# integratedBertha_no_weight.net
KiCad netlist of a schematic drawn in EAGLE
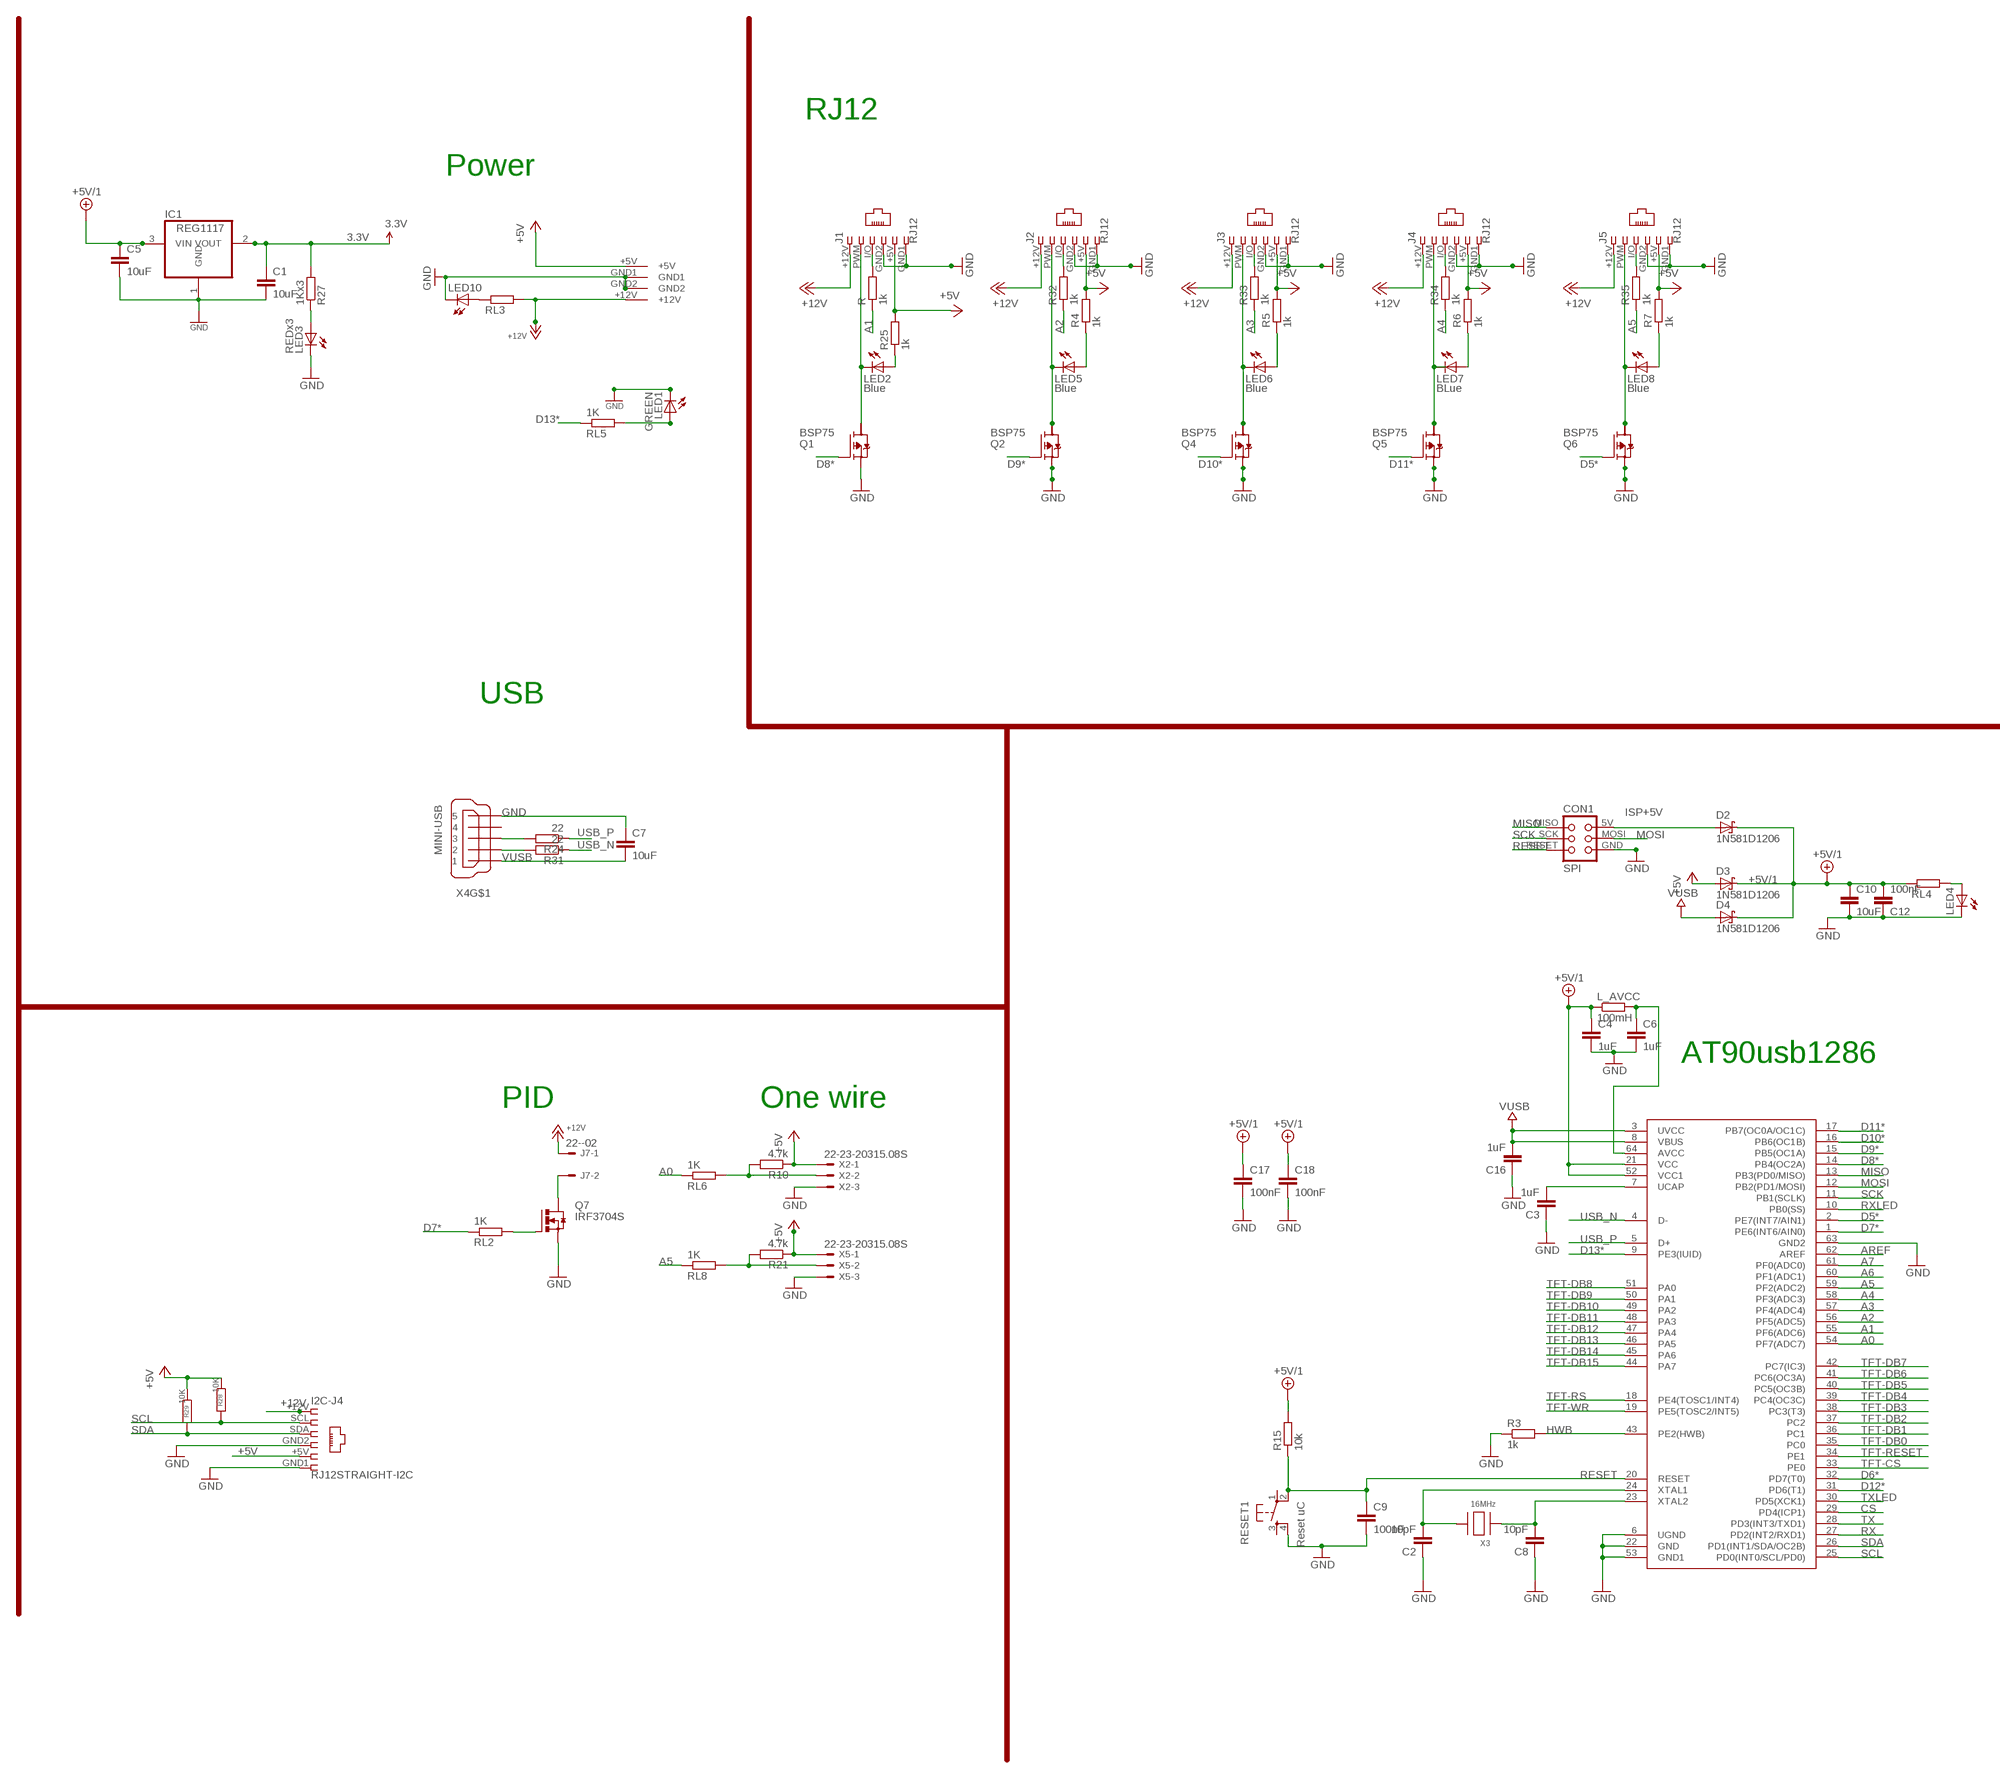
[diagram p0: schematic, sheet 1, part 1 of 2]
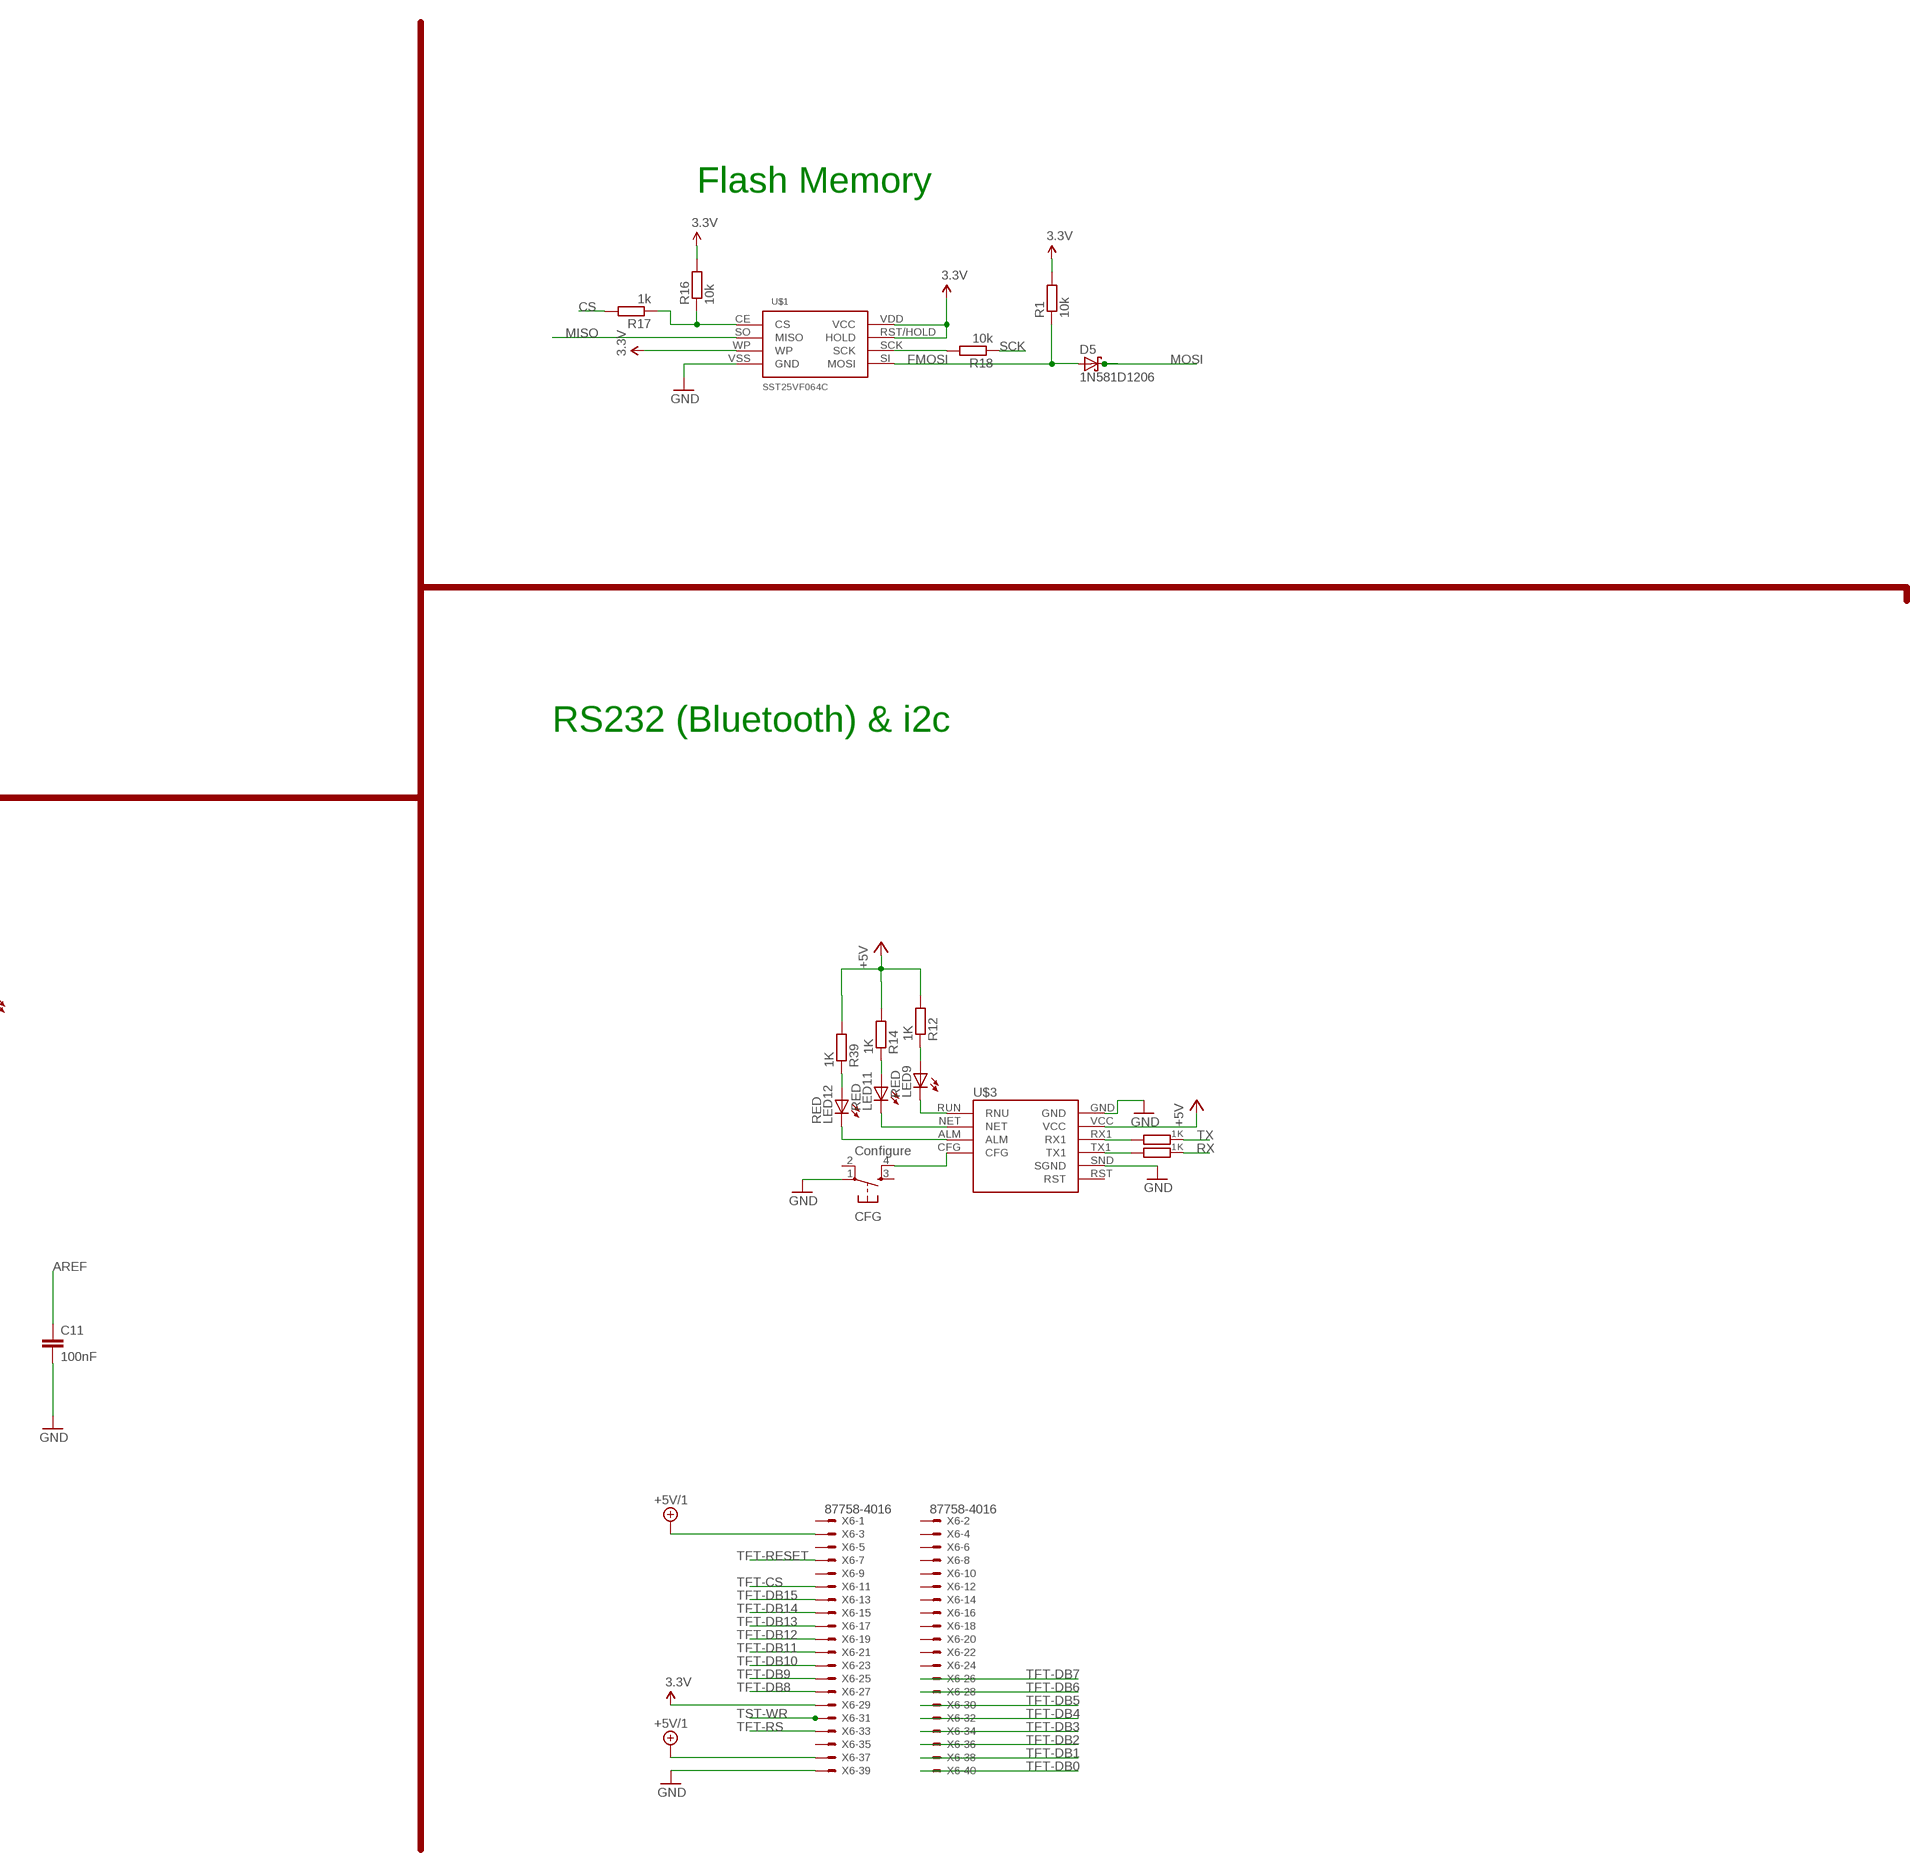
[diagram p1: schematic, sheet 1, part 2 of 2]

(export (version "E")
  (design (tool "Eeschema 10.0.6"))
  (components
    (comp (ref "C1")
      (value "10uF")
      (footprint "eagle-import:C1206")
      (libsource (lib "eagle-import") (part "C-EUC1206"))
    )
    (comp (ref "C2")
      (value "10pF")
      (footprint "eagle-import:C1206")
      (libsource (lib "eagle-import") (part "C-EUC1206"))
    )
    (comp (ref "C3")
      (value "1uF")
      (footprint "eagle-import:C1206")
      (libsource (lib "eagle-import") (part "C-EUC1206"))
    )
    (comp (ref "C4")
      (value "1uF")
      (footprint "eagle-import:C1206")
      (libsource (lib "eagle-import") (part "C-EUC1206"))
    )
    (comp (ref "C5")
      (value "10uF")
      (footprint "eagle-import:C1206")
      (libsource (lib "eagle-import") (part "C-EUC1206"))
    )
    (comp (ref "C6")
      (value "1uF")
      (footprint "eagle-import:C1206")
      (libsource (lib "eagle-import") (part "C-EUC1206"))
    )
    (comp (ref "C7")
      (value "10uF")
      (footprint "eagle-import:C1206")
      (libsource (lib "eagle-import") (part "C-EUC1206"))
    )
    (comp (ref "C8")
      (value "10pF")
      (footprint "eagle-import:C1206")
      (libsource (lib "eagle-import") (part "C-EUC1206"))
    )
    (comp (ref "C9")
      (value "100nF")
      (footprint "eagle-import:C1206")
      (libsource (lib "eagle-import") (part "C-EUC1206"))
    )
    (comp (ref "C10")
      (value "10uF")
      (footprint "eagle-import:C1206")
      (libsource (lib "eagle-import") (part "C-EUC1206"))
    )
    (comp (ref "C11")
      (value "100nF")
      (footprint "eagle-import:C1206")
      (libsource (lib "eagle-import") (part "C-EUC1206"))
    )
    (comp (ref "C12")
      (value "100nF")
      (footprint "eagle-import:C1206")
      (libsource (lib "eagle-import") (part "C-EUC1206"))
    )
    (comp (ref "C16")
      (value "1uF")
      (footprint "eagle-import:C1206")
      (libsource (lib "eagle-import") (part "C-EUC1206"))
    )
    (comp (ref "C17")
      (value "100nF")
      (footprint "eagle-import:C1206")
      (libsource (lib "eagle-import") (part "C-EUC1206"))
    )
    (comp (ref "C18")
      (value "100nF")
      (footprint "eagle-import:C1206")
      (libsource (lib "eagle-import") (part "C-EUC1206"))
    )
    (comp (ref "CFG")
      (value "Configure")
      (footprint "eagle-import:TACTILE_SWITCH_SMD")
      (libsource (lib "eagle-import") (part "TAC_SWITCHSMD"))
    )
    (comp (ref "CON1")
      (value "SPI")
      (footprint "eagle-import:TC2030-MCP-NL")
      (libsource (lib "eagle-import") (part "TINYISPT"))
    )
    (comp (ref "D2")
      (value "1N581D1206")
      (footprint "eagle-import:LED-1206")
      (libsource (lib "eagle-import") (part "1N581D1206"))
    )
    (comp (ref "D3")
      (value "1N581D1206")
      (footprint "eagle-import:LED-1206")
      (libsource (lib "eagle-import") (part "1N581D1206"))
    )
    (comp (ref "D4")
      (value "1N581D1206")
      (footprint "eagle-import:LED-1206")
      (libsource (lib "eagle-import") (part "1N581D1206"))
    )
    (comp (ref "D5")
      (value "1N581D1206")
      (footprint "eagle-import:LED-1206")
      (libsource (lib "eagle-import") (part "1N581D1206"))
    )
    (comp (ref "I2C-J4")
      (value "RJ12STRAIGHT-I2C")
      (footprint "eagle-import:RJ12-STRAIGHT-I2C")
      (libsource (lib "eagle-import") (part "RJ12STRAIGHT-I2C"))
    )
    (comp (ref "IC1")
      (value "REG1117")
      (footprint "eagle-import:SOT223")
      (libsource (lib "eagle-import") (part "REG1117"))
    )
    (comp (ref "J1")
      (value "RJ12")
      (footprint "eagle-import:RJ12-STRAIGHT")
      (libsource (lib "eagle-import") (part "RJ12STRAIGHT"))
    )
    (comp (ref "J2")
      (value "RJ12")
      (footprint "eagle-import:RJ12-STRAIGHT")
      (libsource (lib "eagle-import") (part "RJ12STRAIGHT"))
    )
    (comp (ref "J3")
      (value "RJ12")
      (footprint "eagle-import:RJ12-STRAIGHT")
      (libsource (lib "eagle-import") (part "RJ12STRAIGHT"))
    )
    (comp (ref "J4")
      (value "RJ12")
      (footprint "eagle-import:RJ12-STRAIGHT")
      (libsource (lib "eagle-import") (part "RJ12STRAIGHT"))
    )
    (comp (ref "J5")
      (value "RJ12")
      (footprint "eagle-import:RJ12-STRAIGHT")
      (libsource (lib "eagle-import") (part "RJ12STRAIGHT"))
    )
    (comp (ref "J7")
      (value "22--02")
      (footprint "eagle-import:2-PIN-5.08S")
      (libsource (lib "eagle-import") (part "22-?-02"))
    )
    (comp (ref "LED1")
      (value "GREEN")
      (footprint "eagle-import:CHIPLED_1206")
      (libsource (lib "eagle-import") (part "LEDCHIPLED_1206"))
    )
    (comp (ref "LED2")
      (value "Blue")
      (footprint "eagle-import:CHIPLED_1206")
      (libsource (lib "eagle-import") (part "LEDCHIPLED_1206"))
    )
    (comp (ref "LED3")
      (value "REDx3")
      (footprint "eagle-import:CHIPLED_1206")
      (libsource (lib "eagle-import") (part "LEDCHIPLED_1206"))
    )
    (comp (ref "LED4")
      (value "LEDCHIPLED_1206")
      (footprint "eagle-import:CHIPLED_1206")
      (libsource (lib "eagle-import") (part "LEDCHIPLED_1206"))
    )
    (comp (ref "LED5")
      (value "Blue")
      (footprint "eagle-import:CHIPLED_1206")
      (libsource (lib "eagle-import") (part "LEDCHIPLED_1206"))
    )
    (comp (ref "LED6")
      (value "Blue")
      (footprint "eagle-import:CHIPLED_1206")
      (libsource (lib "eagle-import") (part "LEDCHIPLED_1206"))
    )
    (comp (ref "LED7")
      (value "BLue")
      (footprint "eagle-import:CHIPLED_1206")
      (libsource (lib "eagle-import") (part "LEDCHIPLED_1206"))
    )
    (comp (ref "LED8")
      (value "Blue")
      (footprint "eagle-import:CHIPLED_1206")
      (libsource (lib "eagle-import") (part "LEDCHIPLED_1206"))
    )
    (comp (ref "LED9")
      (value "RED")
      (footprint "eagle-import:CHIPLED_1206")
      (libsource (lib "eagle-import") (part "LEDCHIPLED_1206"))
    )
    (comp (ref "LED10")
      (value "LEDCHIPLED_1206")
      (footprint "eagle-import:CHIPLED_1206")
      (libsource (lib "eagle-import") (part "LEDCHIPLED_1206"))
    )
    (comp (ref "LED11")
      (value "RED")
      (footprint "eagle-import:CHIPLED_1206")
      (libsource (lib "eagle-import") (part "LEDCHIPLED_1206"))
    )
    (comp (ref "LED12")
      (value "RED")
      (footprint "eagle-import:CHIPLED_1206")
      (libsource (lib "eagle-import") (part "LEDCHIPLED_1206"))
    )
    (comp (ref "L_AVCC")
      (value "100mH")
      (footprint "eagle-import:R1206")
      (libsource (lib "eagle-import") (part "resistor_R-EU_R1206"))
    )
    (comp (ref "Q1")
      (value "BSP75")
      (footprint "eagle-import:PG-SOT-223")
      (libsource (lib "eagle-import") (part "BSP613P"))
    )
    (comp (ref "Q2")
      (value "BSP75")
      (footprint "eagle-import:PG-SOT-223")
      (libsource (lib "eagle-import") (part "BSP613P"))
    )
    (comp (ref "Q4")
      (value "BSP75")
      (footprint "eagle-import:PG-SOT-223")
      (libsource (lib "eagle-import") (part "BSP613P"))
    )
    (comp (ref "Q5")
      (value "BSP75")
      (footprint "eagle-import:PG-SOT-223")
      (libsource (lib "eagle-import") (part "BSP613P"))
    )
    (comp (ref "Q6")
      (value "BSP75")
      (footprint "eagle-import:PG-SOT-223")
      (libsource (lib "eagle-import") (part "BSP613P"))
    )
    (comp (ref "Q7")
      (value "IRF3704S")
      (footprint "eagle-import:D2PACK")
      (libsource (lib "eagle-import") (part "IRF3704S"))
    )
    (comp (ref "R")
      (value "1k")
      (footprint "eagle-import:R0805")
      (libsource (lib "eagle-import") (part "R-EU_R0805"))
    )
    (comp (ref "R1")
      (value "10k")
      (footprint "eagle-import:R0805")
      (libsource (lib "eagle-import") (part "R-EU_R0805"))
    )
    (comp (ref "R3")
      (value "1k")
      (footprint "eagle-import:M0805")
      (libsource (lib "eagle-import") (part "resistor_R-EU_M0805"))
    )
    (comp (ref "R4")
      (value "1k")
      (footprint "eagle-import:R0805")
      (libsource (lib "eagle-import") (part "R-EU_R0805"))
    )
    (comp (ref "R5")
      (value "1k")
      (footprint "eagle-import:R0805")
      (libsource (lib "eagle-import") (part "R-EU_R0805"))
    )
    (comp (ref "R6")
      (value "1k")
      (footprint "eagle-import:R0805")
      (libsource (lib "eagle-import") (part "R-EU_R0805"))
    )
    (comp (ref "R7")
      (value "1k")
      (footprint "eagle-import:R0805")
      (libsource (lib "eagle-import") (part "R-EU_R0805"))
    )
    (comp (ref "R8")
      (value "1K")
      (footprint "eagle-import:R0805")
      (libsource (lib "eagle-import") (part "R-EU_R0805"))
    )
    (comp (ref "R10")
      (value "4.7k")
      (footprint "eagle-import:R1206")
      (libsource (lib "eagle-import") (part "resistor_R-EU_R1206"))
    )
    (comp (ref "R11")
      (value "1K")
      (footprint "eagle-import:R0805")
      (libsource (lib "eagle-import") (part "R-EU_R0805"))
    )
    (comp (ref "R12")
      (value "1K")
      (footprint "eagle-import:R0805")
      (libsource (lib "eagle-import") (part "R-EU_R0805"))
    )
    (comp (ref "R14")
      (value "1K")
      (footprint "eagle-import:R0805")
      (libsource (lib "eagle-import") (part "R-EU_R0805"))
    )
    (comp (ref "R15")
      (value "10k")
      (footprint "eagle-import:M0805")
      (libsource (lib "eagle-import") (part "resistor_R-EU_M0805"))
    )
    (comp (ref "R16")
      (value "10k")
      (footprint "eagle-import:R0805")
      (libsource (lib "eagle-import") (part "R-EU_R0805"))
    )
    (comp (ref "R17")
      (value "1k")
      (footprint "eagle-import:R0805")
      (libsource (lib "eagle-import") (part "R-EU_R0805"))
    )
    (comp (ref "R18")
      (value "10k")
      (footprint "eagle-import:R0805")
      (libsource (lib "eagle-import") (part "R-EU_R0805"))
    )
    (comp (ref "R21")
      (value "4.7k")
      (footprint "eagle-import:R1206")
      (libsource (lib "eagle-import") (part "resistor_R-EU_R1206"))
    )
    (comp (ref "R24")
      (value "22")
      (footprint "eagle-import:M1206")
      (libsource (lib "eagle-import") (part "resistor_R-EU_M1206"))
    )
    (comp (ref "R25")
      (value "1k")
      (footprint "eagle-import:R0805")
      (libsource (lib "eagle-import") (part "R-EU_R0805"))
    )
    (comp (ref "R27")
      (value "1Kx3")
      (footprint "eagle-import:R0805")
      (libsource (lib "eagle-import") (part "R-EU_R0805"))
    )
    (comp (ref "R28")
      (value "10K")
      (footprint "eagle-import:M0805")
      (libsource (lib "eagle-import") (part "resistor_R-EU_M0805"))
    )
    (comp (ref "R29")
      (value "10K")
      (footprint "eagle-import:M0805")
      (libsource (lib "eagle-import") (part "resistor_R-EU_M0805"))
    )
    (comp (ref "R31")
      (value "22")
      (footprint "eagle-import:M1206")
      (libsource (lib "eagle-import") (part "resistor_R-EU_M1206"))
    )
    (comp (ref "R32")
      (value "1k")
      (footprint "eagle-import:R0805")
      (libsource (lib "eagle-import") (part "R-EU_R0805"))
    )
    (comp (ref "R33")
      (value "1k")
      (footprint "eagle-import:R0805")
      (libsource (lib "eagle-import") (part "R-EU_R0805"))
    )
    (comp (ref "R34")
      (value "1k")
      (footprint "eagle-import:R0805")
      (libsource (lib "eagle-import") (part "R-EU_R0805"))
    )
    (comp (ref "R35")
      (value "1k")
      (footprint "eagle-import:R0805")
      (libsource (lib "eagle-import") (part "R-EU_R0805"))
    )
    (comp (ref "R39")
      (value "1K")
      (footprint "eagle-import:R0805")
      (libsource (lib "eagle-import") (part "R-EU_R0805"))
    )
    (comp (ref "RESET1")
      (value "Reset uC")
      (footprint "eagle-import:TACTILE_SWITCH_SMD")
      (libsource (lib "eagle-import") (part "TAC_SWITCHSMD"))
    )
    (comp (ref "RL2")
      (value "1K")
      (footprint "eagle-import:R0805")
      (libsource (lib "eagle-import") (part "R-EU_R0805"))
    )
    (comp (ref "RL3")
      (value "R-EU_R0805")
      (footprint "eagle-import:R0805")
      (libsource (lib "eagle-import") (part "R-EU_R0805"))
    )
    (comp (ref "RL4")
      (value "R-EU_R0805")
      (footprint "eagle-import:R0805")
      (libsource (lib "eagle-import") (part "resistor_R-EU_R0805"))
    )
    (comp (ref "RL5")
      (value "1K")
      (footprint "eagle-import:R0805")
      (libsource (lib "eagle-import") (part "R-EU_R0805"))
    )
    (comp (ref "RL6")
      (value "1K")
      (footprint "eagle-import:R0805")
      (libsource (lib "eagle-import") (part "R-EU_R0805"))
    )
    (comp (ref "RL8")
      (value "1K")
      (footprint "eagle-import:R0805")
      (libsource (lib "eagle-import") (part "R-EU_R0805"))
    )
    (comp (ref "U$1")
      (value "SST25VF064C")
      (footprint "eagle-import:SOIC_8-LEAD")
      (libsource (lib "eagle-import") (part "SST25VF064C"))
    )
    (comp (ref "U$2")
      (value "AT90USB1286")
      (footprint "eagle-import:TQFP64")
      (libsource (lib "eagle-import") (part "AT90USB1286TQFP64"))
    )
    (comp (ref "U$3")
      (value "SZ05-ZIGBEETHROUGHHOLE")
      (footprint "eagle-import:SZ05-ZIGBEE4")
      (libsource (lib "eagle-import") (part "SZ05-ZIGBEETHROUGHHOLE"))
    )
    (comp (ref "U$6")
      (value "KPJX-4S-S")
      (footprint "eagle-import:KPJX-4S-S")
      (libsource (lib "eagle-import") (part "KPJX-4S-S"))
    )
    (comp (ref "X2")
      (value "22-23-20315.08S")
      (footprint "eagle-import:3-PIN-5.08S")
      (libsource (lib "eagle-import") (part "22-23-20315.08S"))
    )
    (comp (ref "X3")
      (value "16MHz")
      (footprint "eagle-import:NX6035")
      (libsource (lib "eagle-import") (part "XTALNX6035"))
    )
    (comp (ref "X4")
      (value "MINI-USB")
      (footprint "eagle-import:32005-201")
      (libsource (lib "eagle-import") (part "MINI-USB-SCHIELD-32005-201"))
    )
    (comp (ref "X5")
      (value "22-23-20315.08S")
      (footprint "eagle-import:3-PIN-5.08S")
      (libsource (lib "eagle-import") (part "22-23-20315.08S"))
    )
    (comp (ref "X6")
      (value "87758-4016")
      (footprint "eagle-import:87758-4016")
      (libsource (lib "eagle-import") (part "87758-4016"))
    )
  )
  (nets
    (net (code "1") (name "+5V") (class "Default")
      (node (ref "D3") (pin "A") (pinfunction "A_A") (pintype "passive"))
      (node (ref "I2C-J4") (pin "+5V") (pinfunction "5_+5V") (pintype "bidirectional"))
      (node (ref "J1") (pin "+5V") (pinfunction "5_+5V") (pintype "bidirectional"))
      (node (ref "J2") (pin "+5V") (pinfunction "5_+5V") (pintype "bidirectional"))
      (node (ref "J3") (pin "+5V") (pinfunction "5_+5V") (pintype "bidirectional"))
      (node (ref "J4") (pin "+5V") (pinfunction "5_+5V") (pintype "bidirectional"))
      (node (ref "J5") (pin "+5V") (pinfunction "5_+5V") (pintype "bidirectional"))
      (node (ref "R10") (pin "1") (pinfunction "1_1") (pintype "passive"))
      (node (ref "R12") (pin "2") (pinfunction "2_2") (pintype "passive"))
      (node (ref "R14") (pin "2") (pinfunction "2_2") (pintype "passive"))
      (node (ref "R21") (pin "1") (pinfunction "1_1") (pintype "passive"))
      (node (ref "R25") (pin "2") (pinfunction "2_2") (pintype "passive"))
      (node (ref "R28") (pin "1") (pinfunction "1_1") (pintype "passive"))
      (node (ref "R29") (pin "1") (pinfunction "1_1") (pintype "passive"))
      (node (ref "R39") (pin "2") (pinfunction "2_2") (pintype "passive"))
      (node (ref "R4") (pin "2") (pinfunction "2_2") (pintype "passive"))
      (node (ref "R5") (pin "2") (pinfunction "2_2") (pintype "passive"))
      (node (ref "R6") (pin "2") (pinfunction "2_2") (pintype "passive"))
      (node (ref "R7") (pin "2") (pinfunction "2_2") (pintype "passive"))
      (node (ref "U$3") (pin "VCC") (pinfunction "VCC_VCC") (pintype "bidirectional"))
      (node (ref "U$6") (pin "+5V") (pinfunction "+5V_+5V") (pintype "power_in"))
      (node (ref "X2") (pin "1") (pinfunction "S_1") (pintype "passive"))
      (node (ref "X5") (pin "1") (pinfunction "S_1") (pintype "passive"))
    )
    (net (code "2") (name "+5V{slash}1") (class "Default")
      (node (ref "C10") (pin "1") (pinfunction "1_1") (pintype "passive"))
      (node (ref "C12") (pin "2") (pinfunction "2_2") (pintype "passive"))
      (node (ref "C17") (pin "1") (pinfunction "1_1") (pintype "passive"))
      (node (ref "C18") (pin "1") (pinfunction "1_1") (pintype "passive"))
      (node (ref "C4") (pin "1") (pinfunction "1_1") (pintype "passive"))
      (node (ref "C5") (pin "1") (pinfunction "1_1") (pintype "passive"))
      (node (ref "D2") (pin "C") (pinfunction "C_C") (pintype "passive"))
      (node (ref "D3") (pin "C") (pinfunction "C_C") (pintype "passive"))
      (node (ref "D4") (pin "C") (pinfunction "C_C") (pintype "passive"))
      (node (ref "IC1") (pin "3") (pinfunction "VIN_3") (pintype "input"))
      (node (ref "L_AVCC") (pin "1") (pinfunction "1_1") (pintype "passive"))
      (node (ref "R15") (pin "2") (pinfunction "2_2") (pintype "passive"))
      (node (ref "RL4") (pin "1") (pinfunction "1_1") (pintype "passive"))
      (node (ref "U$2") (pin "21") (pinfunction "VCC_21") (pintype "bidirectional"))
      (node (ref "U$2") (pin "52") (pinfunction "VCC1_52") (pintype "bidirectional"))
      (node (ref "X6") (pin "3") (pinfunction "S_3") (pintype "passive"))
      (node (ref "X6") (pin "37") (pinfunction "S_37") (pintype "passive"))
    )
    (net (code "3") (name "+12V") (class "Default")
      (node (ref "I2C-J4") (pin "+12V") (pinfunction "1_+12V") (pintype "bidirectional"))
      (node (ref "J1") (pin "+12V") (pinfunction "1_+12V") (pintype "bidirectional"))
      (node (ref "J2") (pin "+12V") (pinfunction "1_+12V") (pintype "bidirectional"))
      (node (ref "J3") (pin "+12V") (pinfunction "1_+12V") (pintype "bidirectional"))
      (node (ref "J4") (pin "+12V") (pinfunction "1_+12V") (pintype "bidirectional"))
      (node (ref "J5") (pin "+12V") (pinfunction "1_+12V") (pintype "bidirectional"))
      (node (ref "J7") (pin "1") (pinfunction "S_1") (pintype "passive"))
      (node (ref "RL3") (pin "2") (pinfunction "2_2") (pintype "passive"))
      (node (ref "U$6") (pin "+12V") (pinfunction "+12V_+12V") (pintype "power_in"))
    )
    (net (code "4") (name "/A0") (class "Default")
      (node (ref "RL6") (pin "1") (pinfunction "1_1") (pintype "passive"))
      (node (ref "U$2") (pin "54") (pinfunction "PF7(ADC7)_54") (pintype "bidirectional"))
    )
    (net (code "5") (name "/A1") (class "Default")
      (node (ref "R") (pin "1") (pinfunction "1_1") (pintype "passive"))
      (node (ref "U$2") (pin "55") (pinfunction "PF6(ADC6)_55") (pintype "bidirectional"))
    )
    (net (code "6") (name "/A2") (class "Default")
      (node (ref "R32") (pin "1") (pinfunction "1_1") (pintype "passive"))
      (node (ref "U$2") (pin "56") (pinfunction "PF5(ADC5)_56") (pintype "bidirectional"))
    )
    (net (code "7") (name "/A3") (class "Default")
      (node (ref "R33") (pin "1") (pinfunction "1_1") (pintype "passive"))
      (node (ref "U$2") (pin "57") (pinfunction "PF4(ADC4)_57") (pintype "bidirectional"))
    )
    (net (code "8") (name "/A4") (class "Default")
      (node (ref "R34") (pin "1") (pinfunction "1_1") (pintype "passive"))
      (node (ref "U$2") (pin "58") (pinfunction "PF3(ADC3)_58") (pintype "bidirectional"))
    )
    (net (code "9") (name "/A5") (class "Default")
      (node (ref "R35") (pin "1") (pinfunction "1_1") (pintype "passive"))
      (node (ref "RL8") (pin "1") (pinfunction "1_1") (pintype "passive"))
      (node (ref "U$2") (pin "59") (pinfunction "PF2(ADC2)_59") (pintype "bidirectional"))
    )
    (net (code "10") (name "/A6") (class "Default")
      (node (ref "U$2") (pin "60") (pinfunction "PF1(ADC1)_60") (pintype "bidirectional"))
    )
    (net (code "11") (name "/A7") (class "Default")
      (node (ref "U$2") (pin "61") (pinfunction "PF0(ADC0)_61") (pintype "bidirectional"))
    )
    (net (code "12") (name "/AREF") (class "Default")
      (node (ref "C11") (pin "1") (pinfunction "1_1") (pintype "passive"))
      (node (ref "U$2") (pin "62") (pinfunction "AREF_62") (pintype "bidirectional"))
    )
    (net (code "13") (name "/CS") (class "Default")
      (node (ref "R17") (pin "2") (pinfunction "2_2") (pintype "passive"))
      (node (ref "U$2") (pin "29") (pinfunction "PD4(ICP1)_29") (pintype "bidirectional"))
    )
    (net (code "14") (name "/D5*") (class "Default")
      (node (ref "Q6") (pin "1") (pinfunction "G_1") (pintype "passive"))
      (node (ref "U$2") (pin "2") (pinfunction "PE7(INT7/AIN1)_2") (pintype "bidirectional"))
    )
    (net (code "15") (name "/D6*") (class "Default")
      (node (ref "U$2") (pin "32") (pinfunction "PD7(T0)_32") (pintype "bidirectional"))
    )
    (net (code "16") (name "/D7*") (class "Default")
      (node (ref "RL2") (pin "1") (pinfunction "1_1") (pintype "passive"))
      (node (ref "U$2") (pin "1") (pinfunction "PE6(INT6/AIN0)_1") (pintype "bidirectional"))
    )
    (net (code "17") (name "/D8*") (class "Default")
      (node (ref "Q1") (pin "1") (pinfunction "G_1") (pintype "passive"))
      (node (ref "U$2") (pin "14") (pinfunction "PB4(OC2A)_14") (pintype "bidirectional"))
    )
    (net (code "18") (name "/D9*") (class "Default")
      (node (ref "Q2") (pin "1") (pinfunction "G_1") (pintype "passive"))
      (node (ref "U$2") (pin "15") (pinfunction "PB5(OC1A)_15") (pintype "bidirectional"))
    )
    (net (code "19") (name "/D10*") (class "Default")
      (node (ref "Q4") (pin "1") (pinfunction "G_1") (pintype "passive"))
      (node (ref "U$2") (pin "16") (pinfunction "PB6(OC1B)_16") (pintype "bidirectional"))
    )
    (net (code "20") (name "/D11*") (class "Default")
      (node (ref "Q5") (pin "1") (pinfunction "G_1") (pintype "passive"))
      (node (ref "U$2") (pin "17") (pinfunction "PB7(OC0A/OC1C)_17") (pintype "bidirectional"))
    )
    (net (code "21") (name "/D12*") (class "Default")
      (node (ref "U$2") (pin "31") (pinfunction "PD6(T1)_31") (pintype "bidirectional"))
    )
    (net (code "22") (name "/D13*") (class "Default")
      (node (ref "RL5") (pin "1") (pinfunction "1_1") (pintype "passive"))
      (node (ref "U$2") (pin "9") (pinfunction "PE3(IUID)_9") (pintype "bidirectional"))
    )
    (net (code "23") (name "/FMOSI") (class "Default")
      (node (ref "D5") (pin "A") (pinfunction "A_A") (pintype "passive"))
      (node (ref "R1") (pin "1") (pinfunction "1_1") (pintype "passive"))
      (node (ref "U$1") (pin "SI") (pinfunction "MOSI_SI") (pintype "bidirectional"))
    )
    (net (code "24") (name "/HWB") (class "Default")
      (node (ref "R3") (pin "2") (pinfunction "2_2") (pintype "passive"))
      (node (ref "U$2") (pin "43") (pinfunction "PE2(HWB)_43") (pintype "bidirectional"))
    )
    (net (code "25") (name "/ISP+5V") (class "Default")
      (node (ref "CON1") (pin "5V") (pinfunction "VCC_5V") (pintype "passive"))
      (node (ref "D2") (pin "A") (pinfunction "A_A") (pintype "passive"))
    )
    (net (code "26") (name "/MISO") (class "Default")
      (node (ref "CON1") (pin "MISO") (pinfunction "MISO_MISO") (pintype "passive"))
      (node (ref "U$1") (pin "SO") (pinfunction "MISO_SO") (pintype "bidirectional"))
      (node (ref "U$2") (pin "13") (pinfunction "PB3(PD0/MISO)_13") (pintype "bidirectional"))
    )
    (net (code "27") (name "/MOSI") (class "Default")
      (node (ref "CON1") (pin "MOSI") (pinfunction "MOSI_MOSI") (pintype "passive"))
      (node (ref "D5") (pin "C") (pinfunction "C_C") (pintype "passive"))
      (node (ref "U$2") (pin "12") (pinfunction "PB2(PD1/MOSI)_12") (pintype "bidirectional"))
    )
    (net (code "28") (name "/RESET") (class "Default")
      (node (ref "C9") (pin "1") (pinfunction "1_1") (pintype "passive"))
      (node (ref "CON1") (pin "RESET") (pinfunction "RESET_RESET") (pintype "passive"))
      (node (ref "R15") (pin "1") (pinfunction "1_1") (pintype "passive"))
      (node (ref "RESET1") (pin "2") (pinfunction "2_2") (pintype "passive"))
      (node (ref "U$2") (pin "20") (pinfunction "RESET_20") (pintype "bidirectional"))
    )
    (net (code "29") (name "/RX") (class "Default")
      (node (ref "R8") (pin "1") (pinfunction "1_1") (pintype "passive"))
      (node (ref "U$2") (pin "27") (pinfunction "PD2(INT2/RXD1)_27") (pintype "bidirectional"))
    )
    (net (code "30") (name "/RXLED") (class "Default")
      (node (ref "U$2") (pin "10") (pinfunction "PB0(SS)_10") (pintype "bidirectional"))
    )
    (net (code "31") (name "/SCK") (class "Default")
      (node (ref "CON1") (pin "SCK") (pinfunction "SCK_SCK") (pintype "passive"))
      (node (ref "R18") (pin "1") (pinfunction "1_1") (pintype "passive"))
      (node (ref "U$2") (pin "11") (pinfunction "PB1(SCLK)_11") (pintype "bidirectional"))
    )
    (net (code "32") (name "/SCL") (class "Default")
      (node (ref "I2C-J4") (pin "SCL") (pinfunction "2_SCL") (pintype "bidirectional"))
      (node (ref "R28") (pin "2") (pinfunction "2_2") (pintype "passive"))
      (node (ref "U$2") (pin "25") (pinfunction "PD0(INT0/SCL/PD0)_25") (pintype "bidirectional"))
    )
    (net (code "33") (name "/SDA") (class "Default")
      (node (ref "I2C-J4") (pin "SDA") (pinfunction "3_SDA") (pintype "bidirectional"))
      (node (ref "R29") (pin "2") (pinfunction "2_2") (pintype "passive"))
      (node (ref "U$2") (pin "26") (pinfunction "PD1(INT1/SDA/OC2B)_26") (pintype "bidirectional"))
    )
    (net (code "34") (name "/TFT-CS") (class "Default")
      (node (ref "U$2") (pin "33") (pinfunction "PE0_33") (pintype "bidirectional"))
      (node (ref "X6") (pin "11") (pinfunction "S_11") (pintype "passive"))
    )
    (net (code "35") (name "/TFT-DB0") (class "Default")
      (node (ref "U$2") (pin "35") (pinfunction "PC0_35") (pintype "bidirectional"))
      (node (ref "X6") (pin "40") (pinfunction "S_40") (pintype "passive"))
    )
    (net (code "36") (name "/TFT-DB1") (class "Default")
      (node (ref "U$2") (pin "36") (pinfunction "PC1_36") (pintype "bidirectional"))
      (node (ref "X6") (pin "38") (pinfunction "S_38") (pintype "passive"))
    )
    (net (code "37") (name "/TFT-DB2") (class "Default")
      (node (ref "U$2") (pin "37") (pinfunction "PC2_37") (pintype "bidirectional"))
      (node (ref "X6") (pin "36") (pinfunction "S_36") (pintype "passive"))
    )
    (net (code "38") (name "/TFT-DB3") (class "Default")
      (node (ref "U$2") (pin "38") (pinfunction "PC3(T3)_38") (pintype "bidirectional"))
      (node (ref "X6") (pin "34") (pinfunction "S_34") (pintype "passive"))
    )
    (net (code "39") (name "/TFT-DB4") (class "Default")
      (node (ref "U$2") (pin "39") (pinfunction "PC4(OC3C)_39") (pintype "bidirectional"))
      (node (ref "X6") (pin "32") (pinfunction "S_32") (pintype "passive"))
    )
    (net (code "40") (name "/TFT-DB5") (class "Default")
      (node (ref "U$2") (pin "40") (pinfunction "PC5(OC3B)_40") (pintype "bidirectional"))
      (node (ref "X6") (pin "30") (pinfunction "S_30") (pintype "passive"))
    )
    (net (code "41") (name "/TFT-DB6") (class "Default")
      (node (ref "U$2") (pin "41") (pinfunction "PC6(OC3A)_41") (pintype "bidirectional"))
      (node (ref "X6") (pin "28") (pinfunction "S_28") (pintype "passive"))
    )
    (net (code "42") (name "/TFT-DB7") (class "Default")
      (node (ref "U$2") (pin "42") (pinfunction "PC7(IC3)_42") (pintype "bidirectional"))
      (node (ref "X6") (pin "26") (pinfunction "S_26") (pintype "passive"))
    )
    (net (code "43") (name "/TFT-DB8") (class "Default")
      (node (ref "U$2") (pin "51") (pinfunction "PA0_51") (pintype "bidirectional"))
      (node (ref "X6") (pin "27") (pinfunction "S_27") (pintype "passive"))
    )
    (net (code "44") (name "/TFT-DB9") (class "Default")
      (node (ref "U$2") (pin "50") (pinfunction "PA1_50") (pintype "bidirectional"))
      (node (ref "X6") (pin "25") (pinfunction "S_25") (pintype "passive"))
    )
    (net (code "45") (name "/TFT-DB10") (class "Default")
      (node (ref "U$2") (pin "49") (pinfunction "PA2_49") (pintype "bidirectional"))
      (node (ref "X6") (pin "23") (pinfunction "S_23") (pintype "passive"))
    )
    (net (code "46") (name "/TFT-DB11") (class "Default")
      (node (ref "U$2") (pin "48") (pinfunction "PA3_48") (pintype "bidirectional"))
      (node (ref "X6") (pin "21") (pinfunction "S_21") (pintype "passive"))
    )
    (net (code "47") (name "/TFT-DB12") (class "Default")
      (node (ref "U$2") (pin "47") (pinfunction "PA4_47") (pintype "bidirectional"))
      (node (ref "X6") (pin "19") (pinfunction "S_19") (pintype "passive"))
    )
    (net (code "48") (name "/TFT-DB13") (class "Default")
      (node (ref "U$2") (pin "46") (pinfunction "PA5_46") (pintype "bidirectional"))
      (node (ref "X6") (pin "17") (pinfunction "S_17") (pintype "passive"))
    )
    (net (code "49") (name "/TFT-DB14") (class "Default")
      (node (ref "U$2") (pin "45") (pinfunction "PA6_45") (pintype "bidirectional"))
      (node (ref "X6") (pin "15") (pinfunction "S_15") (pintype "passive"))
    )
    (net (code "50") (name "/TFT-DB15") (class "Default")
      (node (ref "U$2") (pin "44") (pinfunction "PA7_44") (pintype "bidirectional"))
      (node (ref "X6") (pin "13") (pinfunction "S_13") (pintype "passive"))
    )
    (net (code "51") (name "/TFT-RESET") (class "Default")
      (node (ref "U$2") (pin "34") (pinfunction "PE1_34") (pintype "bidirectional"))
      (node (ref "X6") (pin "7") (pinfunction "S_7") (pintype "passive"))
    )
    (net (code "52") (name "/TFT-RS") (class "Default")
      (node (ref "U$2") (pin "18") (pinfunction "PE4(TOSC1/INT4)_18") (pintype "bidirectional"))
      (node (ref "X6") (pin "33") (pinfunction "S_33") (pintype "passive"))
    )
    (net (code "53") (name "/TFT-WR") (class "Default")
      (node (ref "U$2") (pin "19") (pinfunction "PE5(TOSC2/INT5)_19") (pintype "bidirectional"))
    )
    (net (code "54") (name "/TST-WR") (class "Default")
      (node (ref "X6") (pin "31") (pinfunction "S_31") (pintype "passive"))
    )
    (net (code "55") (name "/TX") (class "Default")
      (node (ref "R11") (pin "1") (pinfunction "1_1") (pintype "passive"))
      (node (ref "U$2") (pin "28") (pinfunction "PD3(INT3/TXD1)_28") (pintype "bidirectional"))
    )
    (net (code "56") (name "/TXLED") (class "Default")
      (node (ref "U$2") (pin "30") (pinfunction "PD5(XCK1)_30") (pintype "bidirectional"))
    )
    (net (code "57") (name "/USB_N") (class "Default")
      (node (ref "R31") (pin "1") (pinfunction "1_1") (pintype "passive"))
      (node (ref "U$2") (pin "4") (pinfunction "D-_4") (pintype "bidirectional"))
    )
    (net (code "58") (name "/USB_P") (class "Default")
      (node (ref "R24") (pin "1") (pinfunction "1_1") (pintype "passive"))
      (node (ref "U$2") (pin "5") (pinfunction "D+_5") (pintype "bidirectional"))
    )
    (net (code "59") (name "3.3V") (class "Default")
      (node (ref "C1") (pin "1") (pinfunction "1_1") (pintype "passive"))
      (node (ref "IC1") (pin "2") (pinfunction "VOUT_2") (pintype "output"))
      (node (ref "R1") (pin "2") (pinfunction "2_2") (pintype "passive"))
      (node (ref "R16") (pin "2") (pinfunction "2_2") (pintype "passive"))
      (node (ref "R27") (pin "2") (pinfunction "2_2") (pintype "passive"))
      (node (ref "U$1") (pin "RST/HOLD") (pinfunction "HOLD_RST/HOLD") (pintype "bidirectional"))
      (node (ref "U$1") (pin "VDD") (pinfunction "VCC_VDD") (pintype "bidirectional"))
      (node (ref "U$1") (pin "WP") (pinfunction "WP_WP") (pintype "bidirectional"))
      (node (ref "X6") (pin "29") (pinfunction "S_29") (pintype "passive"))
    )
    (net (code "60") (name "GND") (class "Default")
      (node (ref "C1") (pin "2") (pinfunction "2_2") (pintype "passive"))
      (node (ref "C10") (pin "2") (pinfunction "2_2") (pintype "passive"))
      (node (ref "C11") (pin "2") (pinfunction "2_2") (pintype "passive"))
      (node (ref "C12") (pin "1") (pinfunction "1_1") (pintype "passive"))
      (node (ref "C16") (pin "1") (pinfunction "1_1") (pintype "passive"))
      (node (ref "C17") (pin "2") (pinfunction "2_2") (pintype "passive"))
      (node (ref "C18") (pin "2") (pinfunction "2_2") (pintype "passive"))
      (node (ref "C2") (pin "1") (pinfunction "1_1") (pintype "passive"))
      (node (ref "C3") (pin "1") (pinfunction "1_1") (pintype "passive"))
      (node (ref "C4") (pin "2") (pinfunction "2_2") (pintype "passive"))
      (node (ref "C5") (pin "2") (pinfunction "2_2") (pintype "passive"))
      (node (ref "C6") (pin "2") (pinfunction "2_2") (pintype "passive"))
      (node (ref "C7") (pin "1") (pinfunction "1_1") (pintype "passive"))
      (node (ref "C8") (pin "1") (pinfunction "1_1") (pintype "passive"))
      (node (ref "C9") (pin "2") (pinfunction "2_2") (pintype "passive"))
      (node (ref "CFG") (pin "1") (pinfunction "1_1") (pintype "passive"))
      (node (ref "CON1") (pin "GND") (pinfunction "GND_GND") (pintype "passive"))
      (node (ref "I2C-J4") (pin "GND1") (pinfunction "6_GND1") (pintype "bidirectional"))
      (node (ref "I2C-J4") (pin "GND2") (pinfunction "4_GND2") (pintype "bidirectional"))
      (node (ref "IC1") (pin "1") (pinfunction "GND_1") (pintype "power_in"))
      (node (ref "J1") (pin "GND1") (pinfunction "6_GND1") (pintype "bidirectional"))
      (node (ref "J1") (pin "GND2") (pinfunction "4_GND2") (pintype "bidirectional"))
      (node (ref "J2") (pin "GND1") (pinfunction "6_GND1") (pintype "bidirectional"))
      (node (ref "J2") (pin "GND2") (pinfunction "4_GND2") (pintype "bidirectional"))
      (node (ref "J3") (pin "GND1") (pinfunction "6_GND1") (pintype "bidirectional"))
      (node (ref "J3") (pin "GND2") (pinfunction "4_GND2") (pintype "bidirectional"))
      (node (ref "J4") (pin "GND1") (pinfunction "6_GND1") (pintype "bidirectional"))
      (node (ref "J4") (pin "GND2") (pinfunction "4_GND2") (pintype "bidirectional"))
      (node (ref "J5") (pin "GND1") (pinfunction "6_GND1") (pintype "bidirectional"))
      (node (ref "J5") (pin "GND2") (pinfunction "4_GND2") (pintype "bidirectional"))
      (node (ref "LED1") (pin "C") (pinfunction "C_C") (pintype "passive"))
      (node (ref "LED10") (pin "C") (pinfunction "C_C") (pintype "passive"))
      (node (ref "LED3") (pin "C") (pinfunction "C_C") (pintype "passive"))
      (node (ref "LED4") (pin "C") (pinfunction "C_C") (pintype "passive"))
      (node (ref "Q1") (pin "3") (pinfunction "S_3") (pintype "passive"))
      (node (ref "Q2") (pin "3") (pinfunction "S_3") (pintype "passive"))
      (node (ref "Q4") (pin "3") (pinfunction "S_3") (pintype "passive"))
      (node (ref "Q5") (pin "3") (pinfunction "S_3") (pintype "passive"))
      (node (ref "Q6") (pin "3") (pinfunction "S_3") (pintype "passive"))
      (node (ref "Q7") (pin "3") (pinfunction "S_3") (pintype "passive"))
      (node (ref "R3") (pin "1") (pinfunction "1_1") (pintype "passive"))
      (node (ref "RESET1") (pin "4") (pinfunction "4_4") (pintype "passive"))
      (node (ref "U$1") (pin "VSS") (pinfunction "GND_VSS") (pintype "bidirectional"))
      (node (ref "U$2") (pin "22") (pinfunction "GND_22") (pintype "bidirectional"))
      (node (ref "U$2") (pin "53") (pinfunction "GND1_53") (pintype "bidirectional"))
      (node (ref "U$2") (pin "6") (pinfunction "UGND_6") (pintype "bidirectional"))
      (node (ref "U$2") (pin "63") (pinfunction "GND2_63") (pintype "bidirectional"))
      (node (ref "U$3") (pin "GND") (pinfunction "GND_GND") (pintype "bidirectional"))
      (node (ref "U$3") (pin "SND") (pinfunction "SGND_SND") (pintype "bidirectional"))
      (node (ref "U$6") (pin "GND1") (pinfunction "GND1_GND1") (pintype "input"))
      (node (ref "U$6") (pin "GND2") (pinfunction "GND2_GND2") (pintype "input"))
      (node (ref "X2") (pin "3") (pinfunction "S_3") (pintype "passive"))
      (node (ref "X4") (pin "5") (pinfunction "5_5") (pintype "passive"))
      (node (ref "X5") (pin "3") (pinfunction "S_3") (pintype "passive"))
      (node (ref "X6") (pin "39") (pinfunction "S_39") (pintype "passive"))
    )
    (net (code "61") (name "Net-(CFG-Pad4)") (class "Default")
      (node (ref "CFG") (pin "4") (pinfunction "4_4") (pintype "passive"))
      (node (ref "U$3") (pin "CFG") (pinfunction "CFG_CFG") (pintype "bidirectional"))
    )
    (net (code "62") (name "Net-(J1-2)") (class "Default")
      (node (ref "J1") (pin "PWM") (pinfunction "2_PWM") (pintype "bidirectional"))
      (node (ref "LED2") (pin "C") (pinfunction "C_C") (pintype "passive"))
      (node (ref "Q1") (pin "2") (pinfunction "D_2") (pintype "passive"))
    )
    (net (code "63") (name "Net-(J1-3)") (class "Default")
      (node (ref "J1") (pin "I/O") (pinfunction "3_I/O") (pintype "bidirectional"))
      (node (ref "R") (pin "2") (pinfunction "2_2") (pintype "passive"))
    )
    (net (code "64") (name "Net-(J2-2)") (class "Default")
      (node (ref "J2") (pin "PWM") (pinfunction "2_PWM") (pintype "bidirectional"))
      (node (ref "LED5") (pin "C") (pinfunction "C_C") (pintype "passive"))
      (node (ref "Q2") (pin "2") (pinfunction "D_2") (pintype "passive"))
    )
    (net (code "65") (name "Net-(J2-3)") (class "Default")
      (node (ref "J2") (pin "I/O") (pinfunction "3_I/O") (pintype "bidirectional"))
      (node (ref "R32") (pin "2") (pinfunction "2_2") (pintype "passive"))
    )
    (net (code "66") (name "Net-(J3-2)") (class "Default")
      (node (ref "J3") (pin "PWM") (pinfunction "2_PWM") (pintype "bidirectional"))
      (node (ref "LED6") (pin "C") (pinfunction "C_C") (pintype "passive"))
      (node (ref "Q4") (pin "2") (pinfunction "D_2") (pintype "passive"))
    )
    (net (code "67") (name "Net-(J3-3)") (class "Default")
      (node (ref "J3") (pin "I/O") (pinfunction "3_I/O") (pintype "bidirectional"))
      (node (ref "R33") (pin "2") (pinfunction "2_2") (pintype "passive"))
    )
    (net (code "68") (name "Net-(J4-2)") (class "Default")
      (node (ref "J4") (pin "PWM") (pinfunction "2_PWM") (pintype "bidirectional"))
      (node (ref "LED7") (pin "C") (pinfunction "C_C") (pintype "passive"))
      (node (ref "Q5") (pin "2") (pinfunction "D_2") (pintype "passive"))
    )
    (net (code "69") (name "Net-(J4-3)") (class "Default")
      (node (ref "J4") (pin "I/O") (pinfunction "3_I/O") (pintype "bidirectional"))
      (node (ref "R34") (pin "2") (pinfunction "2_2") (pintype "passive"))
    )
    (net (code "70") (name "Net-(J5-2)") (class "Default")
      (node (ref "J5") (pin "PWM") (pinfunction "2_PWM") (pintype "bidirectional"))
      (node (ref "LED8") (pin "C") (pinfunction "C_C") (pintype "passive"))
      (node (ref "Q6") (pin "2") (pinfunction "D_2") (pintype "passive"))
    )
    (net (code "71") (name "Net-(J5-3)") (class "Default")
      (node (ref "J5") (pin "I/O") (pinfunction "3_I/O") (pintype "bidirectional"))
      (node (ref "R35") (pin "2") (pinfunction "2_2") (pintype "passive"))
    )
    (net (code "72") (name "Net-(J7B-S)") (class "Default")
      (node (ref "J7") (pin "2") (pinfunction "S_2") (pintype "passive"))
      (node (ref "Q7") (pin "2") (pinfunction "D_2") (pintype "passive"))
    )
    (net (code "73") (name "Net-(LED1-PadA)") (class "Default")
      (node (ref "LED1") (pin "A") (pinfunction "A_A") (pintype "passive"))
      (node (ref "RL5") (pin "2") (pinfunction "2_2") (pintype "passive"))
    )
    (net (code "74") (name "Net-(LED2-PadA)") (class "Default")
      (node (ref "LED2") (pin "A") (pinfunction "A_A") (pintype "passive"))
      (node (ref "R25") (pin "1") (pinfunction "1_1") (pintype "passive"))
    )
    (net (code "75") (name "Net-(LED3-PadA)") (class "Default")
      (node (ref "LED3") (pin "A") (pinfunction "A_A") (pintype "passive"))
      (node (ref "R27") (pin "1") (pinfunction "1_1") (pintype "passive"))
    )
    (net (code "76") (name "Net-(LED4-PadA)") (class "Default")
      (node (ref "LED4") (pin "A") (pinfunction "A_A") (pintype "passive"))
      (node (ref "RL4") (pin "2") (pinfunction "2_2") (pintype "passive"))
    )
    (net (code "77") (name "Net-(LED5-PadA)") (class "Default")
      (node (ref "LED5") (pin "A") (pinfunction "A_A") (pintype "passive"))
      (node (ref "R4") (pin "1") (pinfunction "1_1") (pintype "passive"))
    )
    (net (code "78") (name "Net-(LED6-PadA)") (class "Default")
      (node (ref "LED6") (pin "A") (pinfunction "A_A") (pintype "passive"))
      (node (ref "R5") (pin "1") (pinfunction "1_1") (pintype "passive"))
    )
    (net (code "79") (name "Net-(LED7-PadA)") (class "Default")
      (node (ref "LED7") (pin "A") (pinfunction "A_A") (pintype "passive"))
      (node (ref "R6") (pin "1") (pinfunction "1_1") (pintype "passive"))
    )
    (net (code "80") (name "Net-(LED8-PadA)") (class "Default")
      (node (ref "LED8") (pin "A") (pinfunction "A_A") (pintype "passive"))
      (node (ref "R7") (pin "1") (pinfunction "1_1") (pintype "passive"))
    )
    (net (code "81") (name "Net-(LED9-PadA)") (class "Default")
      (node (ref "LED9") (pin "A") (pinfunction "A_A") (pintype "passive"))
      (node (ref "R12") (pin "1") (pinfunction "1_1") (pintype "passive"))
    )
    (net (code "82") (name "Net-(LED10-PadA)") (class "Default")
      (node (ref "LED10") (pin "A") (pinfunction "A_A") (pintype "passive"))
      (node (ref "RL3") (pin "1") (pinfunction "1_1") (pintype "passive"))
    )
    (net (code "83") (name "Net-(LED11-PadA)") (class "Default")
      (node (ref "LED11") (pin "A") (pinfunction "A_A") (pintype "passive"))
      (node (ref "R14") (pin "1") (pinfunction "1_1") (pintype "passive"))
    )
    (net (code "84") (name "Net-(LED11-PadC)") (class "Default")
      (node (ref "LED11") (pin "C") (pinfunction "C_C") (pintype "passive"))
      (node (ref "U$3") (pin "NET") (pinfunction "NET_NET") (pintype "bidirectional"))
    )
    (net (code "85") (name "Net-(LED12-PadA)") (class "Default")
      (node (ref "LED12") (pin "A") (pinfunction "A_A") (pintype "passive"))
      (node (ref "R39") (pin "1") (pinfunction "1_1") (pintype "passive"))
    )
    (net (code "86") (name "Net-(LED12-PadC)") (class "Default")
      (node (ref "LED12") (pin "C") (pinfunction "C_C") (pintype "passive"))
      (node (ref "U$3") (pin "ALM") (pinfunction "ALM_ALM") (pintype "bidirectional"))
    )
    (net (code "87") (name "Net-(Q7-G)") (class "Default")
      (node (ref "Q7") (pin "1") (pinfunction "G_1") (pintype "passive"))
      (node (ref "RL2") (pin "2") (pinfunction "2_2") (pintype "passive"))
    )
    (net (code "88") (name "Net-(R8-Pad2)") (class "Default")
      (node (ref "R8") (pin "2") (pinfunction "2_2") (pintype "passive"))
      (node (ref "U$3") (pin "TX1") (pinfunction "TX1_TX1") (pintype "bidirectional"))
    )
    (net (code "89") (name "Net-(R11-Pad2)") (class "Default")
      (node (ref "R11") (pin "2") (pinfunction "2_2") (pintype "passive"))
      (node (ref "U$3") (pin "RX1") (pinfunction "RX1_RX1") (pintype "bidirectional"))
    )
    (net (code "90") (name "Net-(R18-Pad2)") (class "Default")
      (node (ref "R18") (pin "2") (pinfunction "2_2") (pintype "passive"))
      (node (ref "U$1") (pin "SCK") (pinfunction "SCK_SCK") (pintype "bidirectional"))
    )
    (net (code "91") (name "Net-(R24-Pad2)") (class "Default")
      (node (ref "R24") (pin "2") (pinfunction "2_2") (pintype "passive"))
      (node (ref "X4") (pin "3") (pinfunction "3_3") (pintype "passive"))
    )
    (net (code "92") (name "Net-(R31-Pad2)") (class "Default")
      (node (ref "R31") (pin "2") (pinfunction "2_2") (pintype "passive"))
      (node (ref "X4") (pin "2") (pinfunction "2_2") (pintype "passive"))
    )
    (net (code "93") (name "Net-(U$1-CS)") (class "Default")
      (node (ref "R16") (pin "1") (pinfunction "1_1") (pintype "passive"))
      (node (ref "R17") (pin "1") (pinfunction "1_1") (pintype "passive"))
      (node (ref "U$1") (pin "CE") (pinfunction "CS_CE") (pintype "bidirectional"))
    )
    (net (code "94") (name "Net-(U$2-AVCC)") (class "Default")
      (node (ref "C6") (pin "1") (pinfunction "1_1") (pintype "passive"))
      (node (ref "L_AVCC") (pin "2") (pinfunction "2_2") (pintype "passive"))
      (node (ref "U$2") (pin "64") (pinfunction "AVCC_64") (pintype "bidirectional"))
    )
    (net (code "95") (name "Net-(U$2-UCAP)") (class "Default")
      (node (ref "C3") (pin "2") (pinfunction "2_2") (pintype "passive"))
      (node (ref "U$2") (pin "7") (pinfunction "UCAP_7") (pintype "bidirectional"))
    )
    (net (code "96") (name "Net-(U$2-XTAL1)") (class "Default")
      (node (ref "C2") (pin "2") (pinfunction "2_2") (pintype "passive"))
      (node (ref "U$2") (pin "24") (pinfunction "XTAL1_24") (pintype "bidirectional"))
      (node (ref "X3") (pin "P$2") (pinfunction "P$2_P$2") (pintype "bidirectional"))
    )
    (net (code "97") (name "Net-(U$2-XTAL2)") (class "Default")
      (node (ref "C8") (pin "2") (pinfunction "2_2") (pintype "passive"))
      (node (ref "U$2") (pin "23") (pinfunction "XTAL2_23") (pintype "bidirectional"))
      (node (ref "X3") (pin "P$1") (pinfunction "P$1_P$1") (pintype "bidirectional"))
    )
    (net (code "98") (name "Net-(U$3-RNU)") (class "Default")
      (node (ref "LED9") (pin "C") (pinfunction "C_C") (pintype "passive"))
      (node (ref "U$3") (pin "RUN") (pinfunction "RNU_RUN") (pintype "bidirectional"))
    )
    (net (code "99") (name "Net-(X2B-S)") (class "Default")
      (node (ref "R10") (pin "2") (pinfunction "2_2") (pintype "passive"))
      (node (ref "RL6") (pin "2") (pinfunction "2_2") (pintype "passive"))
      (node (ref "X2") (pin "2") (pinfunction "S_2") (pintype "passive"))
    )
    (net (code "100") (name "Net-(X5B-S)") (class "Default")
      (node (ref "R21") (pin "2") (pinfunction "2_2") (pintype "passive"))
      (node (ref "RL8") (pin "2") (pinfunction "2_2") (pintype "passive"))
      (node (ref "X5") (pin "2") (pinfunction "S_2") (pintype "passive"))
    )
    (net (code "101") (name "VUSB") (class "Default")
      (node (ref "C16") (pin "2") (pinfunction "2_2") (pintype "passive"))
      (node (ref "C7") (pin "2") (pinfunction "2_2") (pintype "passive"))
      (node (ref "D4") (pin "A") (pinfunction "A_A") (pintype "passive"))
      (node (ref "U$2") (pin "3") (pinfunction "UVCC_3") (pintype "bidirectional"))
      (node (ref "U$2") (pin "8") (pinfunction "VBUS_8") (pintype "bidirectional"))
      (node (ref "X4") (pin "1") (pinfunction "1_1") (pintype "passive"))
    )
    (net (code "102") (name "unconnected-(CFG-Pad2)") (class "Default")
      (node (ref "CFG") (pin "2") (pinfunction "2_2") (pintype "passive"))
    )
    (net (code "103") (name "unconnected-(CFG-Pad3)") (class "Default")
      (node (ref "CFG") (pin "3") (pinfunction "3_3") (pintype "passive"))
    )
    (net (code "104") (name "unconnected-(Q1-D-Pad4)") (class "Default")
      (node (ref "Q1") (pin "4") (pinfunction "D_4") (pintype "passive"))
    )
    (net (code "105") (name "unconnected-(Q2-D-Pad4)") (class "Default")
      (node (ref "Q2") (pin "4") (pinfunction "D_4") (pintype "passive"))
    )
    (net (code "106") (name "unconnected-(Q4-D-Pad4)") (class "Default")
      (node (ref "Q4") (pin "4") (pinfunction "D_4") (pintype "passive"))
    )
    (net (code "107") (name "unconnected-(Q5-D-Pad4)") (class "Default")
      (node (ref "Q5") (pin "4") (pinfunction "D_4") (pintype "passive"))
    )
    (net (code "108") (name "unconnected-(Q6-D-Pad4)") (class "Default")
      (node (ref "Q6") (pin "4") (pinfunction "D_4") (pintype "passive"))
    )
    (net (code "109") (name "unconnected-(RESET1-Pad1)") (class "Default")
      (node (ref "RESET1") (pin "1") (pinfunction "1_1") (pintype "passive"))
    )
    (net (code "110") (name "unconnected-(RESET1-Pad3)") (class "Default")
      (node (ref "RESET1") (pin "3") (pinfunction "3_3") (pintype "passive"))
    )
    (net (code "111") (name "unconnected-(U$3-PadRST)") (class "Default")
      (node (ref "U$3") (pin "RST") (pinfunction "RST_RST") (pintype "bidirectional"))
    )
    (net (code "112") (name "unconnected-(X4-Pad4)") (class "Default")
      (node (ref "X4") (pin "4") (pinfunction "4_4") (pintype "passive"))
    )
    (net (code "113") (name "unconnected-(X6A-S-Pad1)") (class "Default")
      (node (ref "X6") (pin "1") (pinfunction "S_1") (pintype "passive"))
    )
    (net (code "114") (name "unconnected-(X6AC-S-Pad35)") (class "Default")
      (node (ref "X6") (pin "35") (pinfunction "S_35") (pintype "passive"))
    )
    (net (code "115") (name "unconnected-(X6AH-S-Pad4)") (class "Default")
      (node (ref "X6") (pin "4") (pinfunction "S_4") (pintype "passive"))
    )
    (net (code "116") (name "unconnected-(X6AJ-S-Pad5)") (class "Default")
      (node (ref "X6") (pin "5") (pinfunction "S_5") (pintype "passive"))
    )
    (net (code "117") (name "unconnected-(X6AK-S-Pad6)") (class "Default")
      (node (ref "X6") (pin "6") (pinfunction "S_6") (pintype "passive"))
    )
    (net (code "118") (name "unconnected-(X6AM-S-Pad8)") (class "Default")
      (node (ref "X6") (pin "8") (pinfunction "S_8") (pintype "passive"))
    )
    (net (code "119") (name "unconnected-(X6AN-S-Pad9)") (class "Default")
      (node (ref "X6") (pin "9") (pinfunction "S_9") (pintype "passive"))
    )
    (net (code "120") (name "unconnected-(X6B-S-Pad10)") (class "Default")
      (node (ref "X6") (pin "10") (pinfunction "S_10") (pintype "passive"))
    )
    (net (code "121") (name "unconnected-(X6D-S-Pad12)") (class "Default")
      (node (ref "X6") (pin "12") (pinfunction "S_12") (pintype "passive"))
    )
    (net (code "122") (name "unconnected-(X6F-S-Pad14)") (class "Default")
      (node (ref "X6") (pin "14") (pinfunction "S_14") (pintype "passive"))
    )
    (net (code "123") (name "unconnected-(X6H-S-Pad16)") (class "Default")
      (node (ref "X6") (pin "16") (pinfunction "S_16") (pintype "passive"))
    )
    (net (code "124") (name "unconnected-(X6J-S-Pad18)") (class "Default")
      (node (ref "X6") (pin "18") (pinfunction "S_18") (pintype "passive"))
    )
    (net (code "125") (name "unconnected-(X6L-S-Pad2)") (class "Default")
      (node (ref "X6") (pin "2") (pinfunction "S_2") (pintype "passive"))
    )
    (net (code "126") (name "unconnected-(X6M-S-Pad20)") (class "Default")
      (node (ref "X6") (pin "20") (pinfunction "S_20") (pintype "passive"))
    )
    (net (code "127") (name "unconnected-(X6O-S-Pad22)") (class "Default")
      (node (ref "X6") (pin "22") (pinfunction "S_22") (pintype "passive"))
    )
    (net (code "128") (name "unconnected-(X6Q-S-Pad24)") (class "Default")
      (node (ref "X6") (pin "24") (pinfunction "S_24") (pintype "passive"))
    )
  )
)
